# 09-Transmitter.net
KiCad netlist of a schematic drawn in Altium Designer
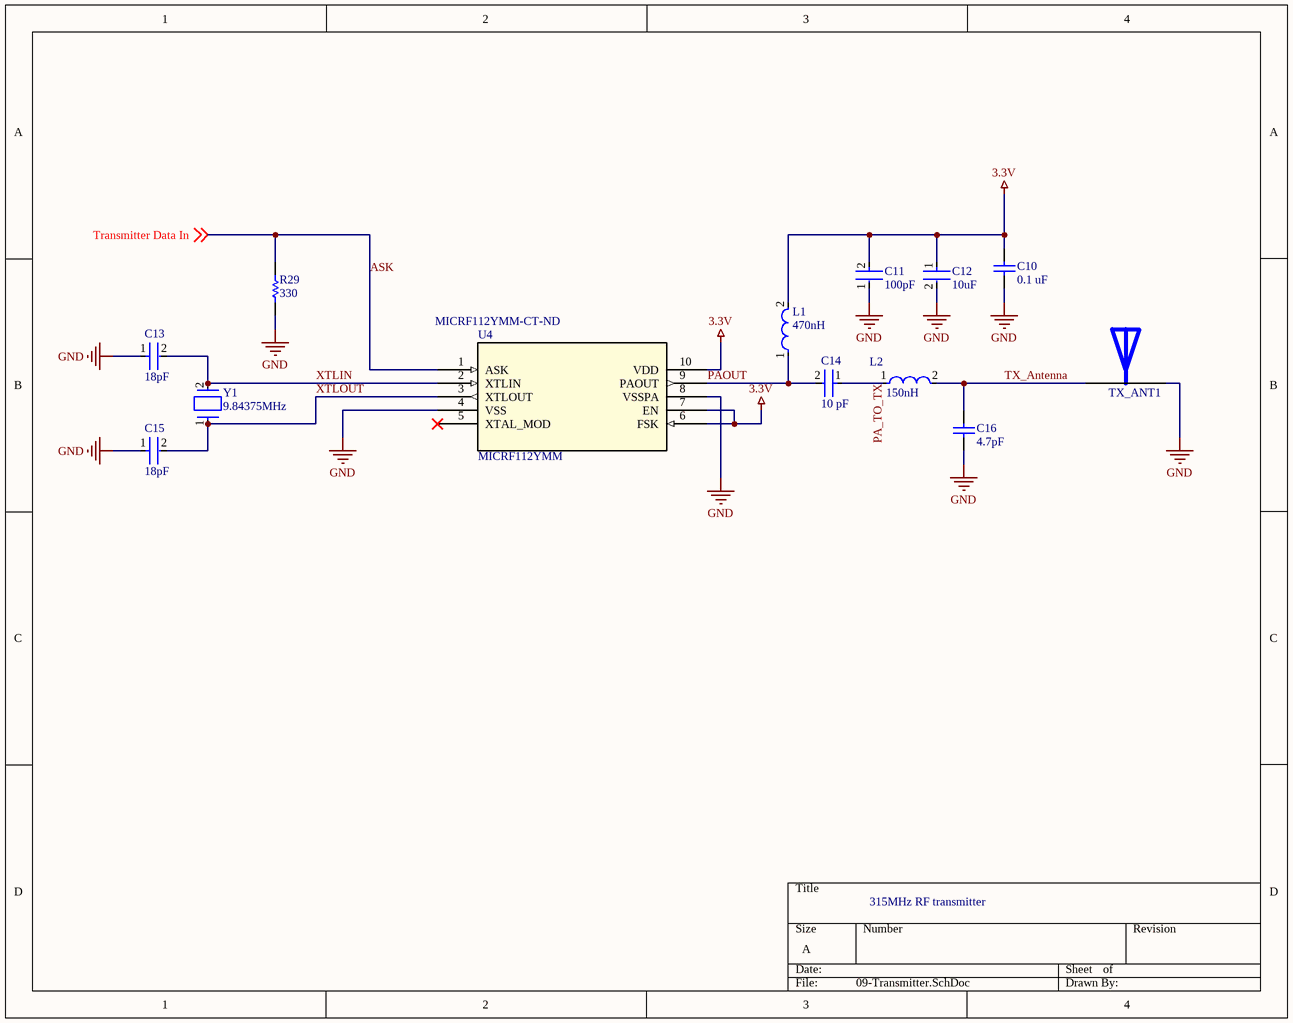
[diagram p0: 09-Transmitter.SchDoc]

(export (version "E")
  (design (tool "Eeschema 10.0.6"))
  (components
    (comp (ref "C10")
      (value "0.1 uF")
      (footprint "CAPC2013X135X45ML10T25")
      (description "Chip Capacitor, 0.1 uF, +/- 10%, 50 V, -55 to 125 degC, 0805 (2012 Metric), RoHS, Tape and Reel")
      (fields (field (name "VOLTAGE") "50V") (field (name "TOLERANCE") "10%"))
      (libsource (lib "Altium Content Vault") (part "CAP-NP-2"))
    )
    (comp (ref "C11")
      (value "100pF")
      (footprint "FP-C0805C-DN-MFG")
      (description "CAP CER 100PF 50V C0G/NP0 0805")
      (fields
        (field (name "OCTOPART") "https://octopart.com/c0805c101j5gactu-kemet-100795")
        (field (name "TOLERANCE") "0.05")
      )
      (libsource (lib "") (part "b4654b650e69147ec39a6b967a45e02_1"))
    )
    (comp (ref "C12")
      (value "10uF")
      (footprint "FP-C0805C-DG-MFG")
      (description "CAP CER 10UF 10V X5R 0805")
      (fields (field (name "TOLERANCE") "10%") (field (name "MANUFACTURER PART NUMBER") "C0805C106K8PACTU"))
      (libsource (lib "Altium Content Vault") (part "11868f565c42a9108669ba33697ecf6"))
    )
    (comp (ref "C13")
      (value "18pF")
      (footprint "FP-C0805C-DN-MFG")
      (description "CAP CER 18PF 50V C0G/NP0 0805")
      (fields
        (field (name "OCTOPART") "https://octopart.com/c0805c180j5gactu-kemet-144810")
        (field (name "TOLERANCE") "0.05")
      )
      (libsource (lib "Altium Content Vault") (part "b4654b650e69147ec39a6b967a45e02"))
    )
    (comp (ref "C14")
      (value "10 pF")
      (footprint "FP-C0805C-DN-MFG")
      (description "Capacitor; Ceramic; Cap 10 pF; Tol 5%; Vol-Rtg 50 VDC; SMT; 0805; COG (NPO); Tape&Reel")
      (fields
        (field (name "OCTOPART") "https://octopart.com/c0805c100j5gactu-kemet-104357")
        (field (name "MANUFACTURER PART NUMBER") "C0805C100J5GACTU")
      )
      (libsource (lib "Altium Content Vault") (part "b4654b650e69147ec39a6b967a45e02"))
    )
    (comp (ref "C15")
      (value "18pF")
      (footprint "FP-C0805C-DN-MFG")
      (description "CAP CER 18PF 50V C0G/NP0 0805")
      (fields
        (field (name "OCTOPART") "https://octopart.com/c0805c180j5gactu-kemet-144810")
        (field (name "TOLERANCE") "0.05")
      )
      (libsource (lib "Altium Content Vault") (part "b4654b650e69147ec39a6b967a45e02"))
    )
    (comp (ref "C16")
      (value "4.7pF")
      (footprint "CAPC2013X140X50NL20T25")
      (fields
        (field (name "MANUFACTURER") "AVX Interconnect / Elco")
        (field (name "PART NUMBER") "08051A4R7CAT2A")
      )
      (libsource (lib "Altium Content Vault") (part "CAP"))
    )
    (comp (ref "L1")
      (value "470nH")
      (footprint "FP-LQW2UAS_00-MFG")
      (description "Wire Wound RF Inductor 470nH ±5% 470mA 1.19Ω 1008 (2520)")
      (fields (field (name "TOLERANCE") "5%"))
      (libsource (lib "Altium Content Vault") (part "725321dda6339637d4d059423bc1c3c"))
    )
    (comp (ref "L2")
      (value "150nH")
      (footprint "FP-LQW2BHN_03-MFG")
      (description "Wire Wound RF Inductor 150nH ±5% 390mA 0.47Ω 0805 (2015)")
      (fields (field (name "TOLERANCE") "5%"))
      (libsource (lib "Altium Content Vault") (part "725321dda6339637d4d059423bc1c3c"))
    )
    (comp (ref "R29")
      (value "330")
      (footprint "RESC2013X60X35ML10T20")
      (description "Chip Resistor, 100 KOhm, +/- 1%, 0.125 W, -55 to 155 degC, 0805 (2012 Metric), RoHS, Tape and Reel")
      (fields (field (name "MANUFACTURER") "Yageo") (field (name "TOLERANCE") "1%"))
      (libsource (lib "Altium Content Vault") (part "RES-2"))
    )
    (comp (ref "TX_ANT1")
      (value "TX Antenna")
      (footprint "TX_Antenna")
      (libsource (lib "team6") (part "TX Antenna"))
    )
    (comp (ref "U4")
      (value "MICRF112YMM")
      (footprint "MSOP10_MC_MCH")
      (description "No Description Available")
      (fields
        (field (name "SUPPLIER PART NUMBER 1") "MICRF112YMM-CT-ND")
        (field (name "COPYRIGHT") "Copyright (C) 2022 Ultra Librarian. All rights reserved.")
      )
      (libsource (lib "MICRF112YMM") (part "MICRF112YMM"))
    )
    (comp (ref "Y1")
      (value "9.84375MHz")
      (footprint "FP-ABM7-MFG")
      (description "Crystal 9.84375MHz ±30ppm 10pF SMD-2 6mm x 3.5mm")
      (libsource (lib "Altium Content Vault") (part "c23a69dc6c9e2f18f2079038eb95dd1"))
    )
  )
  (nets
    (net (code "1") (name "/PAOUT") (class "Default")
      (node (ref "C14") (pin "2") (pinfunction "2_2") (pintype "passive"))
      (node (ref "L1") (pin "1") (pinfunction "1_1") (pintype "passive"))
      (node (ref "U4") (pin "9") (pinfunction "PAOUT_9") (pintype "output"))
    )
    (net (code "2") (name "/PA_TO_TX") (class "Default")
      (node (ref "C14") (pin "1") (pinfunction "1_1") (pintype "passive"))
      (node (ref "L2") (pin "1") (pinfunction "1_1") (pintype "passive"))
    )
    (net (code "3") (name "/TX_Antenna") (class "Default")
      (node (ref "C16") (pin "2") (pinfunction "2_2") (pintype "passive"))
      (node (ref "L2") (pin "2") (pinfunction "2_2") (pintype "passive"))
      (node (ref "TX_ANT1") (pin "1") (pinfunction "1_1") (pintype "passive"))
    )
    (net (code "4") (name "/XTLIN") (class "Default")
      (node (ref "C13") (pin "2") (pinfunction "2_2") (pintype "passive"))
      (node (ref "U4") (pin "2") (pinfunction "XTLIN_2") (pintype "input"))
      (node (ref "Y1") (pin "2") (pinfunction "2_2") (pintype "passive"))
    )
    (net (code "5") (name "/XTLOUT") (class "Default")
      (node (ref "C15") (pin "2") (pinfunction "2_2") (pintype "passive"))
      (node (ref "U4") (pin "3") (pinfunction "XTLOUT_3") (pintype "output"))
      (node (ref "Y1") (pin "1") (pinfunction "1_1") (pintype "passive"))
    )
    (net (code "6") (name "3.3V") (class "Default")
      (node (ref "C10") (pin "1") (pinfunction "1_1") (pintype "passive"))
      (node (ref "C11") (pin "2") (pinfunction "2_2") (pintype "passive"))
      (node (ref "C12") (pin "1") (pinfunction "1_1") (pintype "passive"))
      (node (ref "L1") (pin "2") (pinfunction "2_2") (pintype "passive"))
      (node (ref "U4") (pin "10") (pinfunction "VDD_10") (pintype "power_in"))
      (node (ref "U4") (pin "6") (pinfunction "FSK_6") (pintype "input"))
      (node (ref "U4") (pin "7") (pinfunction "EN_7") (pintype "passive"))
    )
    (net (code "7") (name "GND") (class "Default")
      (node (ref "C10") (pin "2") (pinfunction "2_2") (pintype "passive"))
      (node (ref "C11") (pin "1") (pinfunction "1_1") (pintype "passive"))
      (node (ref "C12") (pin "2") (pinfunction "2_2") (pintype "passive"))
      (node (ref "C13") (pin "1") (pinfunction "1_1") (pintype "passive"))
      (node (ref "C15") (pin "1") (pinfunction "1_1") (pintype "passive"))
      (node (ref "C16") (pin "1") (pinfunction "1_1") (pintype "passive"))
      (node (ref "R29") (pin "1") (pinfunction "1_1") (pintype "passive"))
      (node (ref "TX_ANT1") (pin "2") (pinfunction "2_2") (pintype "passive"))
      (node (ref "U4") (pin "4") (pinfunction "VSS_4") (pintype "power_in"))
      (node (ref "U4") (pin "8") (pinfunction "VSSPA_8") (pintype "power_in"))
    )
    (net (code "8") (name "Transmitter Data In") (class "Default")
      (node (ref "R29") (pin "2") (pinfunction "2_2") (pintype "passive"))
      (node (ref "U4") (pin "1") (pinfunction "ASK_1") (pintype "input"))
    )
    (net (code "9") (name "unconnected-(U4-XTAL_MOD-Pad5)") (class "Default")
      (node (ref "U4") (pin "5") (pinfunction "XTAL_MOD_5") (pintype "passive+no_connect"))
    )
  )
)
